# SCH_Wifi-Marauder_2024-08-15.net
KiCad netlist of a schematic drawn in EasyEDA
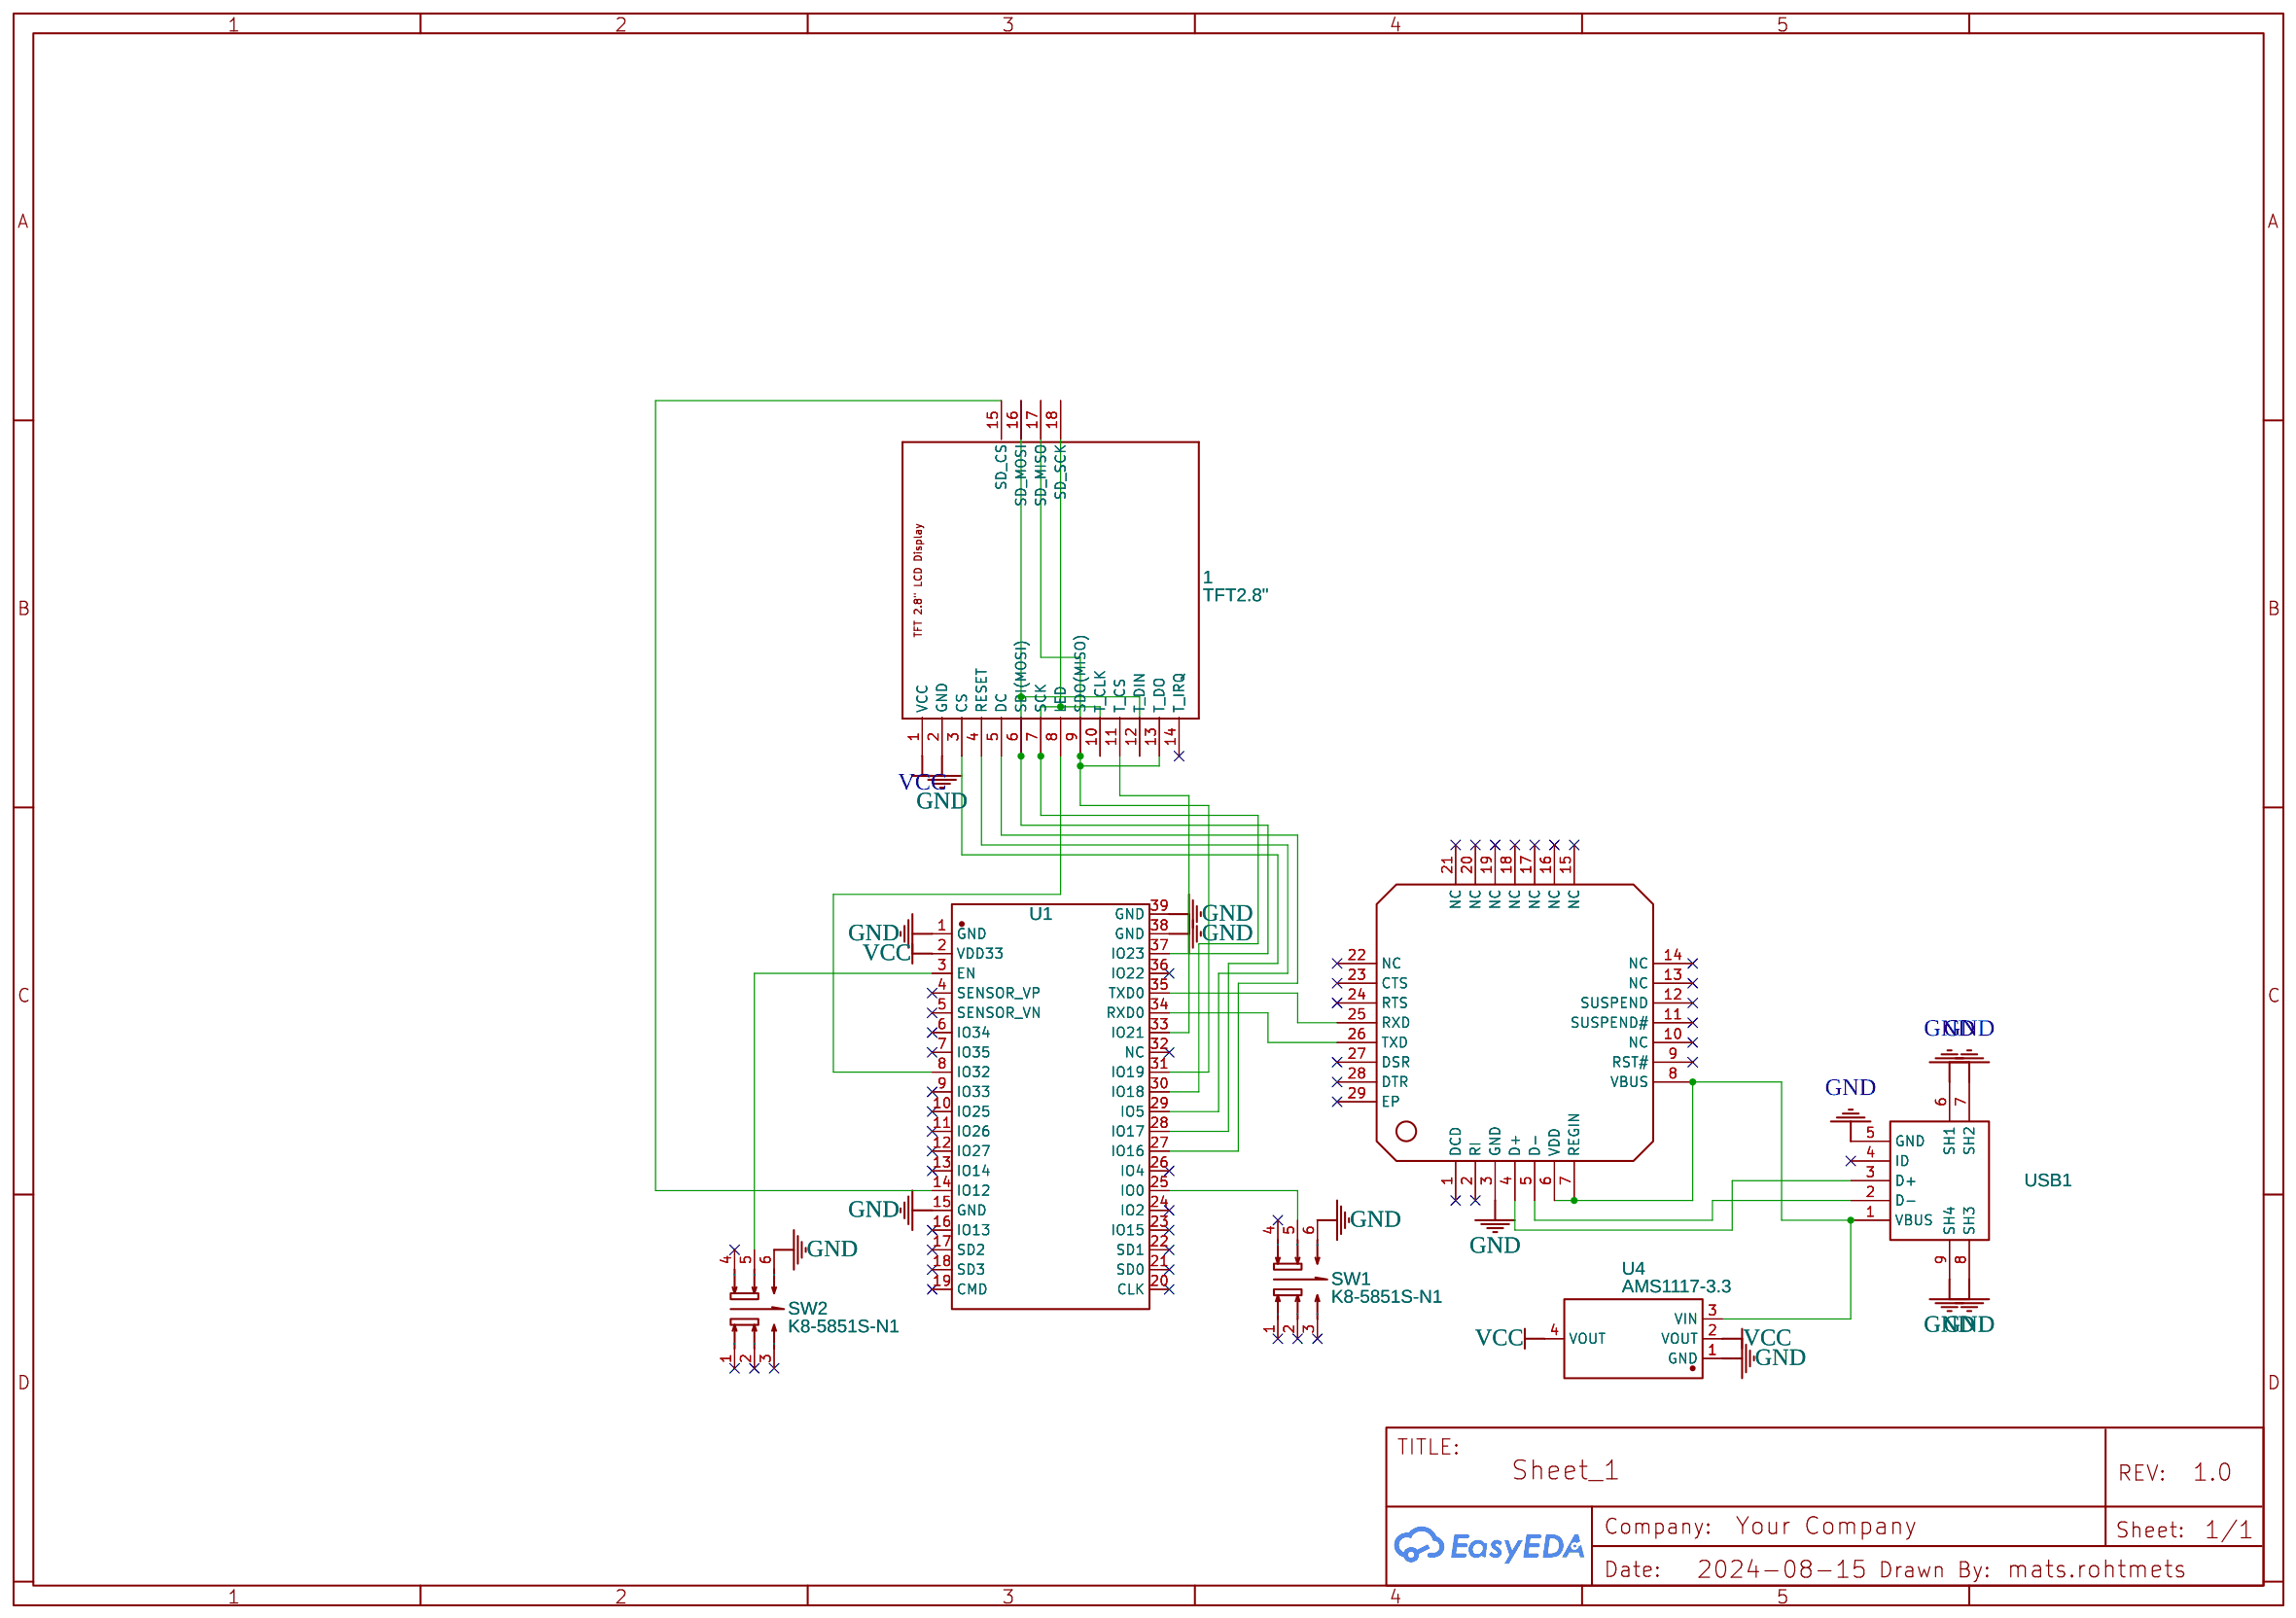
[diagram p0: schematic sheet]

(export (version "E")
  (design (tool "Eeschema 10.0.6"))
  (components
    (comp (ref "1") (value "TFT2.8\"") (libsource (lib "") (part "TFT2.8{dblquote}")))
    (comp (ref "SW1")
      (value "K8-5851S-N1")
      (fields (field (name "Manufacturer") "韩国韩荣"))
      (libsource (lib "") (part "K8-5851S-N1"))
    )
    (comp (ref "SW2")
      (value "K8-5851S-N1")
      (fields (field (name "Manufacturer") "韩国韩荣"))
      (libsource (lib "") (part "K8-5851S-N1"))
    )
    (comp (ref "U1")
      (value "ESP32-WROOM-32U-H4")
      (fields (field (name "Manufacturer") "ESPRESSIF(乐鑫)"))
      (libsource (lib "") (part "ESP32-WROOM-32U-H4"))
    )
    (comp (ref "U3")
      (value "CP2102-GMR")
      (fields (field (name "Manufacturer") "SKYWORKS/SILICON LABS(芯科)"))
      (libsource (lib "") (part "CP2102-GMR"))
    )
    (comp (ref "U4")
      (value "AMS1117-3.3")
      (fields (field (name "Manufacturer") "AMS"))
      (libsource (lib "") (part "AMS1117-3.3"))
    )
    (comp (ref "USB1")
      (value "MICROXNJ")
      (fields (field (name "Manufacturer Part") "MicroXNJ") (field (name "Manufacturer") "SHOU HAN(首韩)"))
      (libsource (lib "") (part "MICROXNJ"))
    )
  )
  (nets
    (net (code "1") (name "GND") (class "Default")
      (node (ref "1") (pin "2") (pinfunction "GND_2") (pintype "bidirectional"))
      (node (ref "SW1") (pin "6") (pinfunction "6_6") (pintype "unspecified"))
      (node (ref "SW2") (pin "6") (pinfunction "6_6") (pintype "unspecified"))
      (node (ref "U1") (pin "1") (pinfunction "GND_1") (pintype "unspecified"))
      (node (ref "U1") (pin "15") (pinfunction "GND_15") (pintype "unspecified"))
      (node (ref "U1") (pin "38") (pinfunction "GND_38") (pintype "unspecified"))
      (node (ref "U1") (pin "39") (pinfunction "GND_39") (pintype "unspecified"))
      (node (ref "U3") (pin "3") (pinfunction "GND_3") (pintype "unspecified"))
      (node (ref "U4") (pin "1") (pinfunction "GND_1") (pintype "unspecified"))
      (node (ref "USB1") (pin "5") (pinfunction "GND_5") (pintype "unspecified"))
      (node (ref "USB1") (pin "6") (pinfunction "SH1_6") (pintype "unspecified"))
      (node (ref "USB1") (pin "7") (pinfunction "SH2_7") (pintype "unspecified"))
      (node (ref "USB1") (pin "8") (pinfunction "SH3_8") (pintype "unspecified"))
      (node (ref "USB1") (pin "9") (pinfunction "SH4_9") (pintype "unspecified"))
    )
    (net (code "2") (name "Net-(1-CS)") (class "Default")
      (node (ref "1") (pin "3") (pinfunction "CS_3") (pintype "bidirectional"))
      (node (ref "U1") (pin "28") (pinfunction "IO17_28") (pintype "unspecified"))
    )
    (net (code "3") (name "Net-(1-DC)") (class "Default")
      (node (ref "1") (pin "5") (pinfunction "DC_5") (pintype "bidirectional"))
      (node (ref "U1") (pin "27") (pinfunction "IO16_27") (pintype "unspecified"))
    )
    (net (code "4") (name "Net-(1-LED)") (class "Default")
      (node (ref "1") (pin "8") (pinfunction "LED_8") (pintype "bidirectional"))
      (node (ref "U1") (pin "8") (pinfunction "IO32_8") (pintype "unspecified"))
    )
    (net (code "5") (name "Net-(1-RESET)") (class "Default")
      (node (ref "1") (pin "4") (pinfunction "RESET_4") (pintype "bidirectional"))
      (node (ref "U1") (pin "29") (pinfunction "IO5_29") (pintype "unspecified"))
    )
    (net (code "6") (name "Net-(1-SCK)") (class "Default")
      (node (ref "1") (pin "10") (pinfunction "T_CLK_10") (pintype "bidirectional"))
      (node (ref "1") (pin "18") (pinfunction "SD_SCK_18") (pintype "bidirectional"))
      (node (ref "1") (pin "7") (pinfunction "SCK_7") (pintype "bidirectional"))
      (node (ref "U1") (pin "30") (pinfunction "IO18_30") (pintype "unspecified"))
    )
    (net (code "7") (name "Net-(1-SDI(MOSI))") (class "Default")
      (node (ref "1") (pin "12") (pinfunction "T_DIN_12") (pintype "bidirectional"))
      (node (ref "1") (pin "16") (pinfunction "SD_MOSI_16") (pintype "bidirectional"))
      (node (ref "1") (pin "6") (pinfunction "SDI(MOSI)_6") (pintype "bidirectional"))
      (node (ref "U1") (pin "37") (pinfunction "IO23_37") (pintype "unspecified"))
    )
    (net (code "8") (name "Net-(1-SDO(MISO))") (class "Default")
      (node (ref "1") (pin "13") (pinfunction "T_DO_13") (pintype "bidirectional"))
      (node (ref "1") (pin "17") (pinfunction "SD_MISO_17") (pintype "bidirectional"))
      (node (ref "1") (pin "9") (pinfunction "SDO(MISO)_9") (pintype "bidirectional"))
      (node (ref "U1") (pin "31") (pinfunction "IO19_31") (pintype "unspecified"))
    )
    (net (code "9") (name "Net-(1-SD_CS)") (class "Default")
      (node (ref "1") (pin "15") (pinfunction "SD_CS_15") (pintype "bidirectional"))
      (node (ref "U1") (pin "14") (pinfunction "IO12_14") (pintype "unspecified"))
    )
    (net (code "10") (name "Net-(1-T_CS)") (class "Default")
      (node (ref "1") (pin "11") (pinfunction "T_CS_11") (pintype "bidirectional"))
      (node (ref "U1") (pin "33") (pinfunction "IO21_33") (pintype "unspecified"))
    )
    (net (code "11") (name "Net-(U1-EN)") (class "Default")
      (node (ref "SW2") (pin "5") (pinfunction "5_5") (pintype "unspecified"))
      (node (ref "U1") (pin "3") (pinfunction "EN_3") (pintype "unspecified"))
    )
    (net (code "12") (name "Net-(U1-IO0)") (class "Default")
      (node (ref "SW1") (pin "5") (pinfunction "5_5") (pintype "unspecified"))
      (node (ref "U1") (pin "25") (pinfunction "IO0_25") (pintype "unspecified"))
    )
    (net (code "13") (name "Net-(U1-RXD0)") (class "Default")
      (node (ref "U1") (pin "34") (pinfunction "RXD0_34") (pintype "unspecified"))
      (node (ref "U3") (pin "26") (pinfunction "TXD_26") (pintype "unspecified"))
    )
    (net (code "14") (name "Net-(U1-TXD0)") (class "Default")
      (node (ref "U1") (pin "35") (pinfunction "TXD0_35") (pintype "unspecified"))
      (node (ref "U3") (pin "25") (pinfunction "RXD_25") (pintype "unspecified"))
    )
    (net (code "15") (name "Net-(U3-D+)") (class "Default")
      (node (ref "U3") (pin "4") (pinfunction "D+_4") (pintype "unspecified"))
      (node (ref "USB1") (pin "3") (pinfunction "D+_3") (pintype "unspecified"))
    )
    (net (code "16") (name "Net-(U3-D-)") (class "Default")
      (node (ref "U3") (pin "5") (pinfunction "D-_5") (pintype "unspecified"))
      (node (ref "USB1") (pin "2") (pinfunction "D-_2") (pintype "unspecified"))
    )
    (net (code "17") (name "Net-(U3-REGIN)") (class "Default")
      (node (ref "U3") (pin "6") (pinfunction "VDD_6") (pintype "unspecified"))
      (node (ref "U3") (pin "7") (pinfunction "REGIN_7") (pintype "unspecified"))
      (node (ref "U3") (pin "8") (pinfunction "VBUS_8") (pintype "unspecified"))
      (node (ref "U4") (pin "3") (pinfunction "VIN_3") (pintype "unspecified"))
      (node (ref "USB1") (pin "1") (pinfunction "VBUS_1") (pintype "unspecified"))
    )
    (net (code "18") (name "VCC") (class "Default")
      (node (ref "1") (pin "1") (pinfunction "VCC_1") (pintype "bidirectional"))
      (node (ref "U1") (pin "2") (pinfunction "VDD33_2") (pintype "unspecified"))
      (node (ref "U4") (pin "2") (pinfunction "VOUT_2") (pintype "unspecified"))
      (node (ref "U4") (pin "4") (pinfunction "VOUT_4") (pintype "unspecified"))
    )
    (net (code "19") (name "unconnected-(1-T_IRQ-Pad14)") (class "Default")
      (node (ref "1") (pin "14") (pinfunction "T_IRQ_14") (pintype "bidirectional+no_connect"))
    )
    (net (code "20") (name "unconnected-(SW1-Pad1)") (class "Default")
      (node (ref "SW1") (pin "1") (pinfunction "1_1") (pintype "unspecified+no_connect"))
    )
    (net (code "21") (name "unconnected-(SW1-Pad2)") (class "Default")
      (node (ref "SW1") (pin "2") (pinfunction "2_2") (pintype "unspecified+no_connect"))
    )
    (net (code "22") (name "unconnected-(SW1-Pad3)") (class "Default")
      (node (ref "SW1") (pin "3") (pinfunction "3_3") (pintype "unspecified+no_connect"))
    )
    (net (code "23") (name "unconnected-(SW1-Pad4)") (class "Default")
      (node (ref "SW1") (pin "4") (pinfunction "4_4") (pintype "unspecified+no_connect"))
    )
    (net (code "24") (name "unconnected-(SW2-Pad1)") (class "Default")
      (node (ref "SW2") (pin "1") (pinfunction "1_1") (pintype "unspecified+no_connect"))
    )
    (net (code "25") (name "unconnected-(SW2-Pad2)") (class "Default")
      (node (ref "SW2") (pin "2") (pinfunction "2_2") (pintype "unspecified+no_connect"))
    )
    (net (code "26") (name "unconnected-(SW2-Pad3)") (class "Default")
      (node (ref "SW2") (pin "3") (pinfunction "3_3") (pintype "unspecified+no_connect"))
    )
    (net (code "27") (name "unconnected-(SW2-Pad4)") (class "Default")
      (node (ref "SW2") (pin "4") (pinfunction "4_4") (pintype "unspecified+no_connect"))
    )
    (net (code "28") (name "unconnected-(U1-CLK-Pad20)") (class "Default")
      (node (ref "U1") (pin "20") (pinfunction "CLK_20") (pintype "unspecified+no_connect"))
    )
    (net (code "29") (name "unconnected-(U1-CMD-Pad19)") (class "Default")
      (node (ref "U1") (pin "19") (pinfunction "CMD_19") (pintype "unspecified+no_connect"))
    )
    (net (code "30") (name "unconnected-(U1-IO2-Pad24)") (class "Default")
      (node (ref "U1") (pin "24") (pinfunction "IO2_24") (pintype "unspecified+no_connect"))
    )
    (net (code "31") (name "unconnected-(U1-IO4-Pad26)") (class "Default")
      (node (ref "U1") (pin "26") (pinfunction "IO4_26") (pintype "unspecified+no_connect"))
    )
    (net (code "32") (name "unconnected-(U1-IO13-Pad16)") (class "Default")
      (node (ref "U1") (pin "16") (pinfunction "IO13_16") (pintype "unspecified+no_connect"))
    )
    (net (code "33") (name "unconnected-(U1-IO14-Pad13)") (class "Default")
      (node (ref "U1") (pin "13") (pinfunction "IO14_13") (pintype "unspecified+no_connect"))
    )
    (net (code "34") (name "unconnected-(U1-IO15-Pad23)") (class "Default")
      (node (ref "U1") (pin "23") (pinfunction "IO15_23") (pintype "unspecified+no_connect"))
    )
    (net (code "35") (name "unconnected-(U1-IO22-Pad36)") (class "Default")
      (node (ref "U1") (pin "36") (pinfunction "IO22_36") (pintype "unspecified+no_connect"))
    )
    (net (code "36") (name "unconnected-(U1-IO25-Pad10)") (class "Default")
      (node (ref "U1") (pin "10") (pinfunction "IO25_10") (pintype "unspecified+no_connect"))
    )
    (net (code "37") (name "unconnected-(U1-IO26-Pad11)") (class "Default")
      (node (ref "U1") (pin "11") (pinfunction "IO26_11") (pintype "unspecified+no_connect"))
    )
    (net (code "38") (name "unconnected-(U1-IO27-Pad12)") (class "Default")
      (node (ref "U1") (pin "12") (pinfunction "IO27_12") (pintype "unspecified+no_connect"))
    )
    (net (code "39") (name "unconnected-(U1-IO33-Pad9)") (class "Default")
      (node (ref "U1") (pin "9") (pinfunction "IO33_9") (pintype "unspecified+no_connect"))
    )
    (net (code "40") (name "unconnected-(U1-IO34-Pad6)") (class "Default")
      (node (ref "U1") (pin "6") (pinfunction "IO34_6") (pintype "unspecified+no_connect"))
    )
    (net (code "41") (name "unconnected-(U1-IO35-Pad7)") (class "Default")
      (node (ref "U1") (pin "7") (pinfunction "IO35_7") (pintype "unspecified+no_connect"))
    )
    (net (code "42") (name "unconnected-(U1-NC-Pad32)") (class "Default")
      (node (ref "U1") (pin "32") (pinfunction "NC_32") (pintype "unspecified+no_connect"))
    )
    (net (code "43") (name "unconnected-(U1-SD0-Pad21)") (class "Default")
      (node (ref "U1") (pin "21") (pinfunction "SD0_21") (pintype "unspecified+no_connect"))
    )
    (net (code "44") (name "unconnected-(U1-SD1-Pad22)") (class "Default")
      (node (ref "U1") (pin "22") (pinfunction "SD1_22") (pintype "unspecified+no_connect"))
    )
    (net (code "45") (name "unconnected-(U1-SD2-Pad17)") (class "Default")
      (node (ref "U1") (pin "17") (pinfunction "SD2_17") (pintype "unspecified+no_connect"))
    )
    (net (code "46") (name "unconnected-(U1-SD3-Pad18)") (class "Default")
      (node (ref "U1") (pin "18") (pinfunction "SD3_18") (pintype "unspecified+no_connect"))
    )
    (net (code "47") (name "unconnected-(U1-SENSOR_VN-Pad5)") (class "Default")
      (node (ref "U1") (pin "5") (pinfunction "SENSOR_VN_5") (pintype "unspecified+no_connect"))
    )
    (net (code "48") (name "unconnected-(U1-SENSOR_VP-Pad4)") (class "Default")
      (node (ref "U1") (pin "4") (pinfunction "SENSOR_VP_4") (pintype "unspecified+no_connect"))
    )
    (net (code "49") (name "unconnected-(U3-CTS-Pad23)") (class "Default")
      (node (ref "U3") (pin "23") (pinfunction "CTS_23") (pintype "unspecified+no_connect"))
    )
    (net (code "50") (name "unconnected-(U3-DCD-Pad1)") (class "Default")
      (node (ref "U3") (pin "1") (pinfunction "DCD_1") (pintype "unspecified+no_connect"))
    )
    (net (code "51") (name "unconnected-(U3-DSR-Pad27)") (class "Default")
      (node (ref "U3") (pin "27") (pinfunction "DSR_27") (pintype "unspecified+no_connect"))
    )
    (net (code "52") (name "unconnected-(U3-DTR-Pad28)") (class "Default")
      (node (ref "U3") (pin "28") (pinfunction "DTR_28") (pintype "unspecified+no_connect"))
    )
    (net (code "53") (name "unconnected-(U3-EP-Pad29)") (class "Default")
      (node (ref "U3") (pin "29") (pinfunction "EP_29") (pintype "unspecified+no_connect"))
    )
    (net (code "54") (name "unconnected-(U3-NC-Pad10)") (class "Default")
      (node (ref "U3") (pin "10") (pinfunction "NC_10") (pintype "unspecified+no_connect"))
    )
    (net (code "55") (name "unconnected-(U3-NC-Pad13)") (class "Default")
      (node (ref "U3") (pin "13") (pinfunction "NC_13") (pintype "unspecified+no_connect"))
    )
    (net (code "56") (name "unconnected-(U3-NC-Pad14)") (class "Default")
      (node (ref "U3") (pin "14") (pinfunction "NC_14") (pintype "unspecified+no_connect"))
    )
    (net (code "57") (name "unconnected-(U3-NC-Pad15)") (class "Default")
      (node (ref "U3") (pin "15") (pinfunction "NC_15") (pintype "unspecified+no_connect"))
    )
    (net (code "58") (name "unconnected-(U3-NC-Pad16)") (class "Default")
      (node (ref "U3") (pin "16") (pinfunction "NC_16") (pintype "unspecified+no_connect"))
    )
    (net (code "59") (name "unconnected-(U3-NC-Pad17)") (class "Default")
      (node (ref "U3") (pin "17") (pinfunction "NC_17") (pintype "unspecified+no_connect"))
    )
    (net (code "60") (name "unconnected-(U3-NC-Pad18)") (class "Default")
      (node (ref "U3") (pin "18") (pinfunction "NC_18") (pintype "unspecified+no_connect"))
    )
    (net (code "61") (name "unconnected-(U3-NC-Pad19)") (class "Default")
      (node (ref "U3") (pin "19") (pinfunction "NC_19") (pintype "unspecified+no_connect"))
    )
    (net (code "62") (name "unconnected-(U3-NC-Pad20)") (class "Default")
      (node (ref "U3") (pin "20") (pinfunction "NC_20") (pintype "unspecified+no_connect"))
    )
    (net (code "63") (name "unconnected-(U3-NC-Pad21)") (class "Default")
      (node (ref "U3") (pin "21") (pinfunction "NC_21") (pintype "unspecified+no_connect"))
    )
    (net (code "64") (name "unconnected-(U3-NC-Pad22)") (class "Default")
      (node (ref "U3") (pin "22") (pinfunction "NC_22") (pintype "unspecified+no_connect"))
    )
    (net (code "65") (name "unconnected-(U3-RI-Pad2)") (class "Default")
      (node (ref "U3") (pin "2") (pinfunction "RI_2") (pintype "unspecified+no_connect"))
    )
    (net (code "66") (name "unconnected-(U3-RST#-Pad9)") (class "Default")
      (node (ref "U3") (pin "9") (pinfunction "RST#_9") (pintype "unspecified+no_connect"))
    )
    (net (code "67") (name "unconnected-(U3-RTS-Pad24)") (class "Default")
      (node (ref "U3") (pin "24") (pinfunction "RTS_24") (pintype "unspecified+no_connect"))
    )
    (net (code "68") (name "unconnected-(U3-SUSPEND#-Pad11)") (class "Default")
      (node (ref "U3") (pin "11") (pinfunction "SUSPEND#_11") (pintype "unspecified+no_connect"))
    )
    (net (code "69") (name "unconnected-(U3-SUSPEND-Pad12)") (class "Default")
      (node (ref "U3") (pin "12") (pinfunction "SUSPEND_12") (pintype "unspecified+no_connect"))
    )
    (net (code "70") (name "unconnected-(USB1-ID-Pad4)") (class "Default")
      (node (ref "USB1") (pin "4") (pinfunction "ID_4") (pintype "unspecified+no_connect"))
    )
  )
)
